# EEPROM.net
KiCad netlist of a schematic drawn in Altium Designer
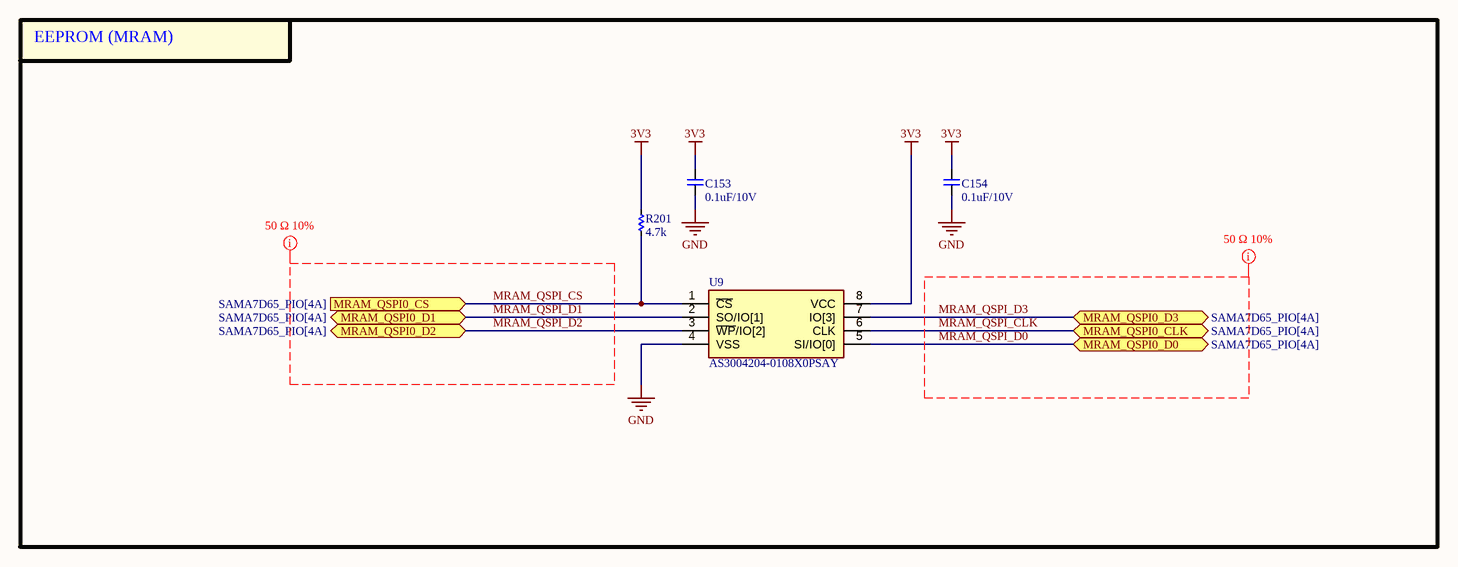
[diagram p0: EEPROM.SchDoc]

(export (version "E")
  (design (tool "Eeschema 10.0.6"))
  (components
    (comp (ref "C153")
      (value "0.1uF/10V")
      (footprint "CAP_C_1005X50_L")
      (description "CAP CHIP")
      (libsource (lib "IFBschelib") (part "_CAP_C_2"))
    )
    (comp (ref "C154")
      (value "0.1uF/10V")
      (footprint "CAP_C_1005X50_L")
      (description "CAP CHIP")
      (libsource (lib "IFBschelib") (part "_CAP_C_2"))
    )
    (comp (ref "R201")
      (value "4.7k")
      (footprint "RES_C_1005x30_L")
      (description "RES")
      (libsource (lib "IFBschelib") (part "_RES_B_2"))
    )
    (comp (ref "U9")
      (value "AS3004204-0108X0PSAY")
      (footprint "SOIC127P790X216-8N")
      (fields (field (name "MOUSER PART NUMBER") "793-30042040108X0PSY"))
      (libsource (lib "IFBschelib") (part "AS3004204-0108X0PSAY"))
    )
  )
  (nets
    (net (code "1") (name "/MRAM_QSPI_CLK") (class "Default")
      (node (ref "U9") (pin "6") (pinfunction "CLK_6") (pintype "passive"))
    )
    (net (code "2") (name "/MRAM_QSPI_CS") (class "Default")
      (node (ref "R201") (pin "2") (pinfunction "2_2") (pintype "passive"))
      (node (ref "U9") (pin "1") (pinfunction "~{CS}_1") (pintype "passive"))
    )
    (net (code "3") (name "/MRAM_QSPI_D0") (class "Default")
      (node (ref "U9") (pin "5") (pinfunction "SI/IO[0]_5") (pintype "passive"))
    )
    (net (code "4") (name "/MRAM_QSPI_D1") (class "Default")
      (node (ref "U9") (pin "2") (pinfunction "SO/IO[1]_2") (pintype "passive"))
    )
    (net (code "5") (name "/MRAM_QSPI_D2") (class "Default")
      (node (ref "U9") (pin "3") (pinfunction "~{WP}/IO[2]_3") (pintype "passive"))
    )
    (net (code "6") (name "/MRAM_QSPI_D3") (class "Default")
      (node (ref "U9") (pin "7") (pinfunction "IO[3]_7") (pintype "passive"))
    )
    (net (code "7") (name "3V3") (class "Default")
      (node (ref "C153") (pin "2") (pinfunction "2_2") (pintype "passive"))
      (node (ref "C154") (pin "2") (pinfunction "2_2") (pintype "passive"))
      (node (ref "R201") (pin "1") (pinfunction "1_1") (pintype "passive"))
      (node (ref "U9") (pin "8") (pinfunction "VCC_8") (pintype "passive"))
    )
    (net (code "8") (name "GND") (class "Default")
      (node (ref "C153") (pin "1") (pinfunction "1_1") (pintype "passive"))
      (node (ref "C154") (pin "1") (pinfunction "1_1") (pintype "passive"))
      (node (ref "U9") (pin "4") (pinfunction "VSS_4") (pintype "passive"))
    )
  )
)
